# PFC_v1b.net
KiCad netlist of a schematic drawn in EAGLE
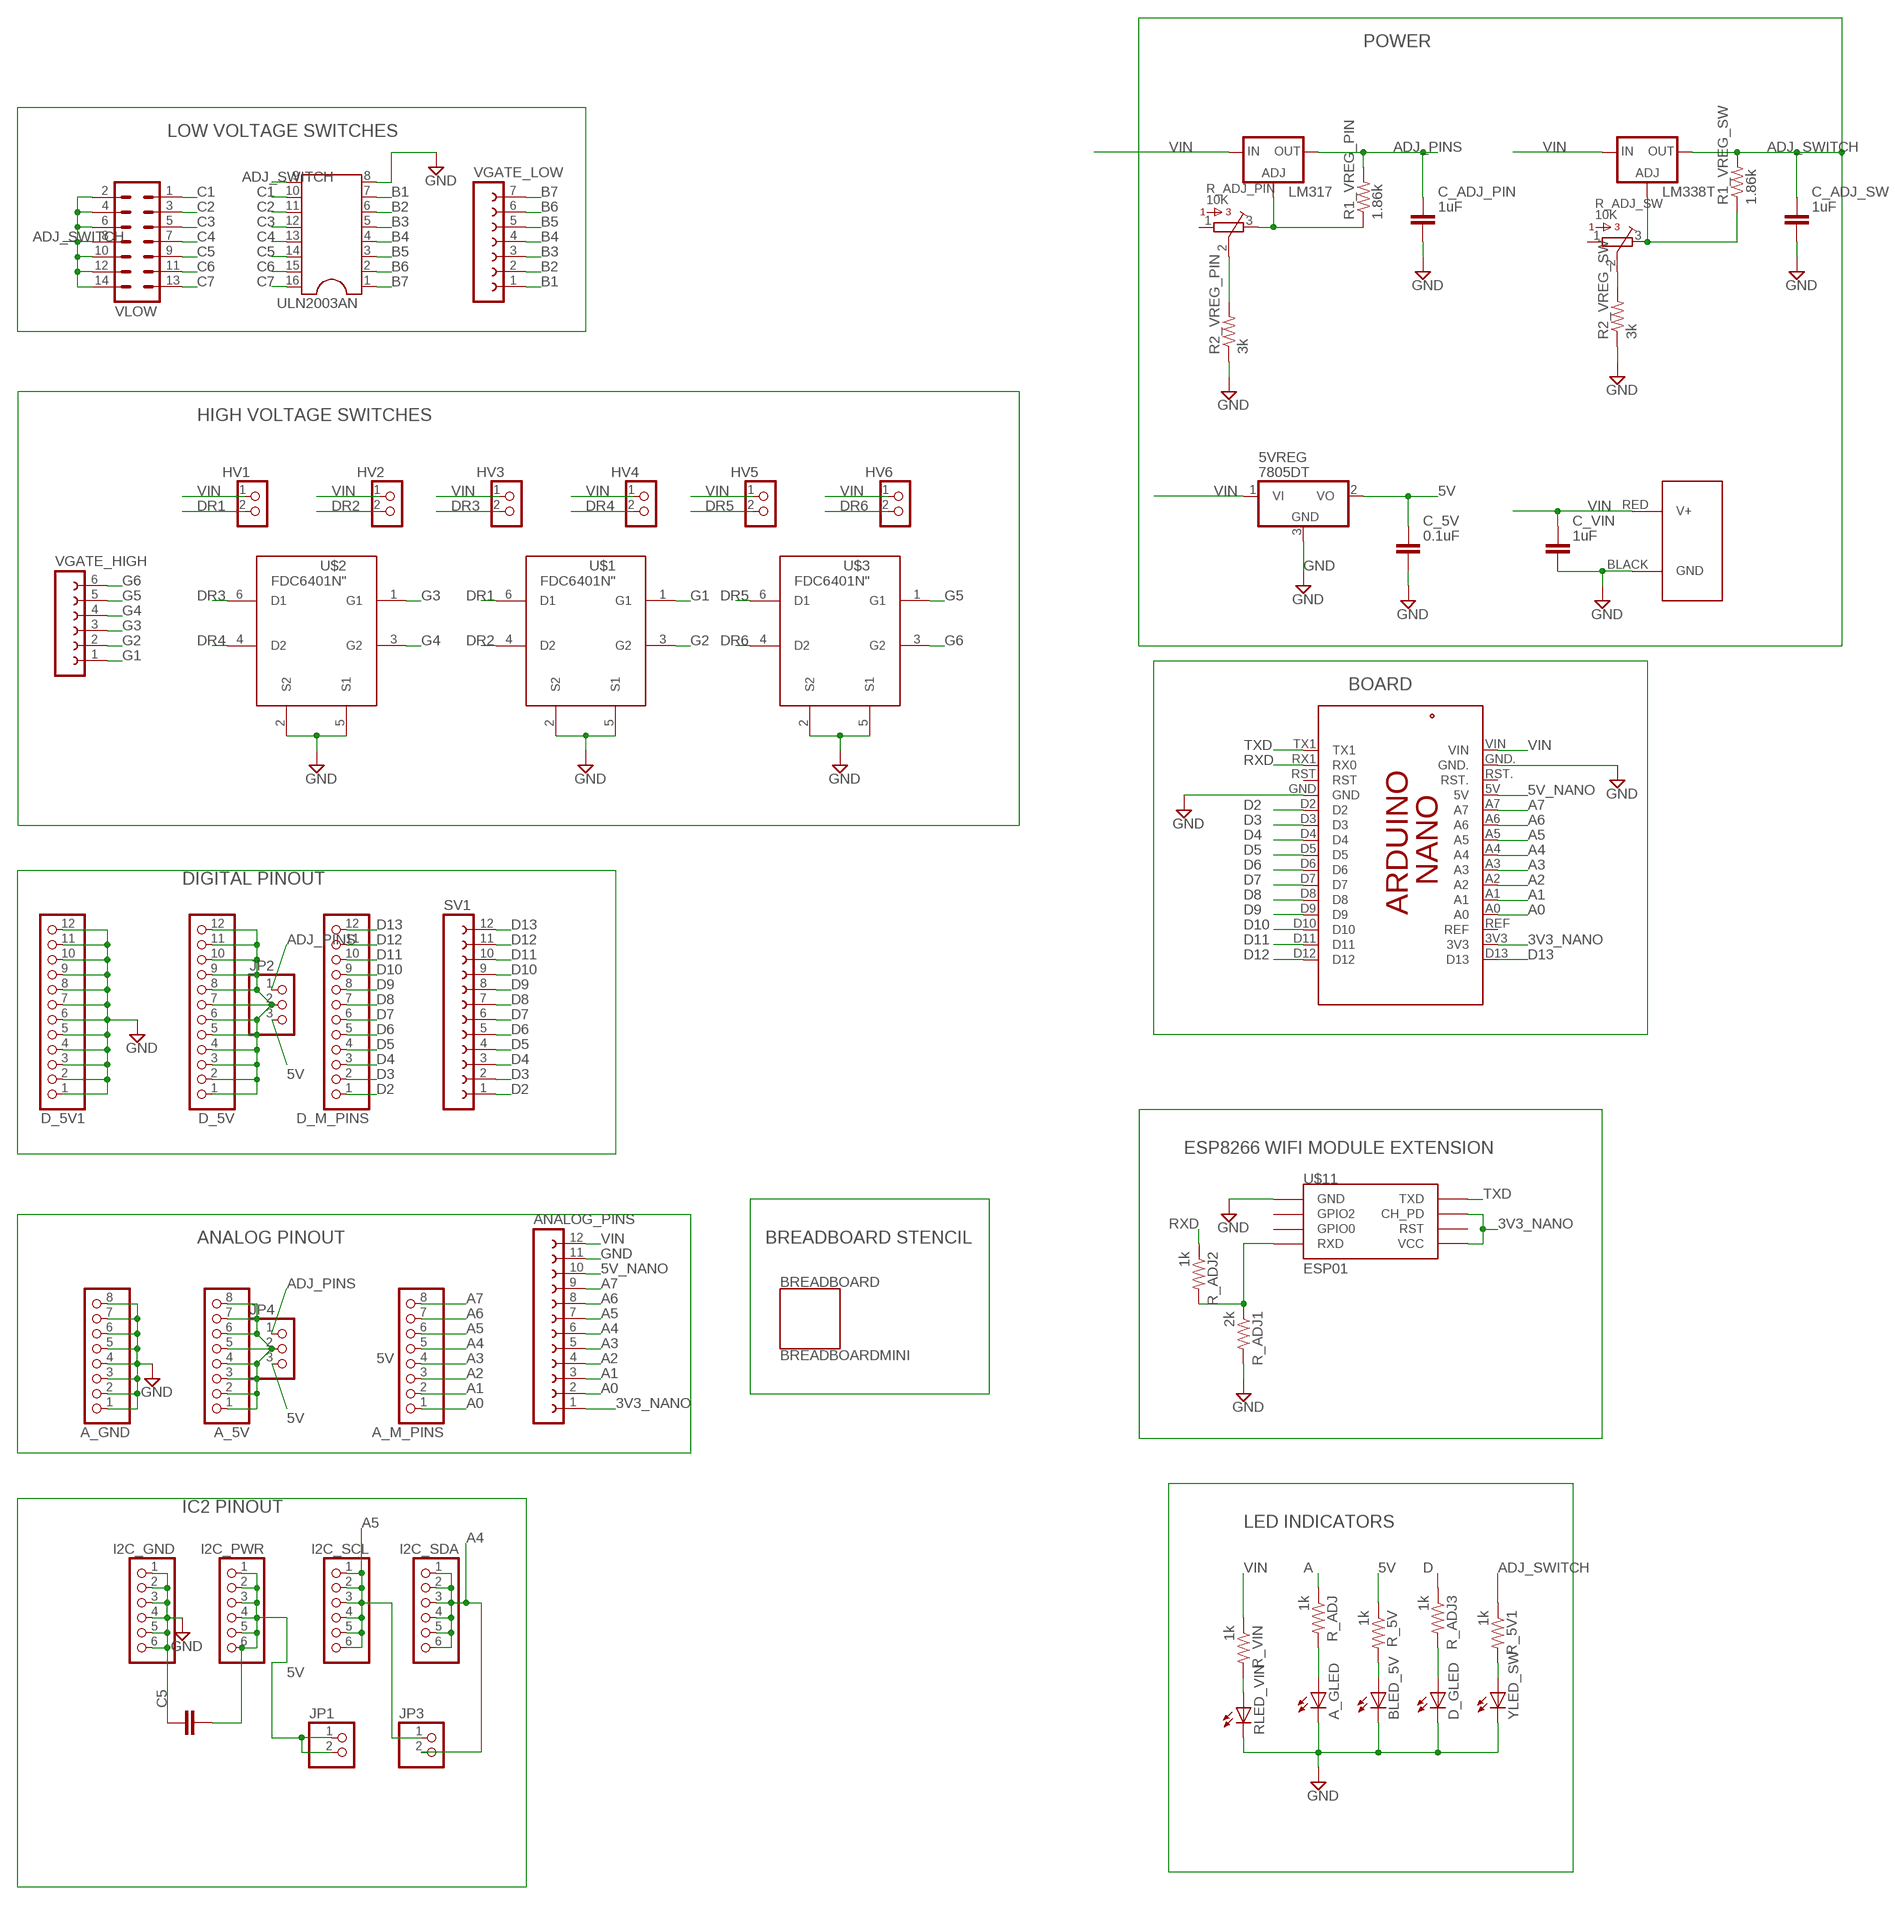
[diagram p0: schematic, sheet 1]

(export (version "E")
  (design (tool "Eeschema 10.0.6"))
  (components
    (comp (ref "5VREG")
      (value "7805DT")
      (footprint "eagle-import:TO252")
      (libsource (lib "eagle-import") (part "78DT05"))
    )
    (comp (ref "ANALOG_PINS")
      (value "FE12-1")
      (footprint "eagle-import:FE12")
      (libsource (lib "eagle-import") (part "FE12-1"))
    )
    (comp (ref "A_5V")
      (value "PINHD-1X8CLEANBIG")
      (footprint "eagle-import:1X08-CLEANBIG")
      (libsource (lib "eagle-import") (part "PINHD-1X8CLEANBIG"))
    )
    (comp (ref "A_GLED")
      (value "LEDCHIP-LED0603")
      (footprint "eagle-import:CHIP-LED0603")
      (libsource (lib "eagle-import") (part "LEDCHIP-LED0603"))
    )
    (comp (ref "A_GND")
      (value "PINHD-1X8CLEANBIG")
      (footprint "eagle-import:1X08-CLEANBIG")
      (libsource (lib "eagle-import") (part "PINHD-1X8CLEANBIG"))
    )
    (comp (ref "A_M_PINS")
      (value "PINHD-1X8CLEANBIG")
      (footprint "eagle-import:1X08-CLEANBIG")
      (libsource (lib "eagle-import") (part "PINHD-1X8CLEANBIG"))
    )
    (comp (ref "BLED_5V")
      (value "LEDCHIP-LED0603")
      (footprint "eagle-import:CHIP-LED0603")
      (libsource (lib "eagle-import") (part "LEDCHIP-LED0603"))
    )
    (comp (ref "BREADBOARD")
      (value "BREADBOARDMINI")
      (footprint "eagle-import:BREADBOARD-MINI")
      (libsource (lib "eagle-import") (part "BREADBOARDMINI"))
    )
    (comp (ref "C5")
      (value "CAPACITOR_NPOL-0603")
      (footprint "eagle-import:C603")
      (libsource (lib "eagle-import") (part "CAPACITOR_NPOL-0603"))
    )
    (comp (ref "C_5V")
      (value "0.1uF")
      (footprint "eagle-import:C603")
      (libsource (lib "eagle-import") (part "CAPACITOR_NPOL-0603"))
    )
    (comp (ref "C_ADJ_PIN")
      (value "1uF")
      (footprint "eagle-import:C603")
      (libsource (lib "eagle-import") (part "CAPACITOR_NPOL-0603"))
    )
    (comp (ref "C_ADJ_SW")
      (value "1uF")
      (footprint "eagle-import:C603")
      (libsource (lib "eagle-import") (part "CAPACITOR_NPOL-0603"))
    )
    (comp (ref "C_VIN")
      (value "1uF")
      (footprint "eagle-import:C603")
      (libsource (lib "eagle-import") (part "CAPACITOR_NPOL-0603"))
    )
    (comp (ref "D_5V")
      (value "PINHD-1X12-CB")
      (footprint "eagle-import:1X12-CB")
      (libsource (lib "eagle-import") (part "PINHD-1X12-CB"))
    )
    (comp (ref "D_5V1")
      (value "PINHD-1X12-CB")
      (footprint "eagle-import:1X12-CB")
      (libsource (lib "eagle-import") (part "PINHD-1X12-CB"))
    )
    (comp (ref "D_GLED")
      (value "LEDCHIP-LED0603")
      (footprint "eagle-import:CHIP-LED0603")
      (libsource (lib "eagle-import") (part "LEDCHIP-LED0603"))
    )
    (comp (ref "D_M_PINS")
      (value "PINHD-1X12-CB")
      (footprint "eagle-import:1X12-CB")
      (libsource (lib "eagle-import") (part "PINHD-1X12-CB"))
    )
    (comp (ref "HV1")
      (value "PINHD-2X1")
      (footprint "eagle-import:2X01")
      (libsource (lib "eagle-import") (part "PINHD-2X1"))
    )
    (comp (ref "HV2")
      (value "PINHD-2X1")
      (footprint "eagle-import:2X01")
      (libsource (lib "eagle-import") (part "PINHD-2X1"))
    )
    (comp (ref "HV3")
      (value "PINHD-2X1")
      (footprint "eagle-import:2X01")
      (libsource (lib "eagle-import") (part "PINHD-2X1"))
    )
    (comp (ref "HV4")
      (value "PINHD-2X1")
      (footprint "eagle-import:2X01")
      (libsource (lib "eagle-import") (part "PINHD-2X1"))
    )
    (comp (ref "HV5")
      (value "PINHD-2X1")
      (footprint "eagle-import:2X01")
      (libsource (lib "eagle-import") (part "PINHD-2X1"))
    )
    (comp (ref "HV6")
      (value "PINHD-2X1")
      (footprint "eagle-import:2X01")
      (libsource (lib "eagle-import") (part "PINHD-2X1"))
    )
    (comp (ref "I2C_GND")
      (value "PINHD-1X6CLEAN")
      (footprint "eagle-import:1X06-CLEAN")
      (libsource (lib "eagle-import") (part "PINHD-1X6CLEAN"))
    )
    (comp (ref "I2C_PWR")
      (value "PINHD-1X6CLEAN")
      (footprint "eagle-import:1X06-CLEAN")
      (libsource (lib "eagle-import") (part "PINHD-1X6CLEAN"))
    )
    (comp (ref "I2C_SCL")
      (value "PINHD-1X6CLEAN")
      (footprint "eagle-import:1X06-CLEAN")
      (libsource (lib "eagle-import") (part "PINHD-1X6CLEAN"))
    )
    (comp (ref "I2C_SDA")
      (value "PINHD-1X6CLEAN")
      (footprint "eagle-import:1X06-CLEAN")
      (libsource (lib "eagle-import") (part "PINHD-1X6CLEAN"))
    )
    (comp (ref "J1")
      (value "POWERPOLE_POWER25A_HORIZONTAL_G2")
      (footprint "eagle-import:POWERPOLE_PAIR_25A_HORIZ_G2")
      (libsource (lib "eagle-import") (part "POWERPOLE_POWER25A_HORIZONTAL_G2"))
    )
    (comp (ref "JP1")
      (value "HEADER-1X2ROUND")
      (footprint "eagle-import:1X02_ROUND")
      (libsource (lib "eagle-import") (part "HEADER-1X2ROUND"))
    )
    (comp (ref "JP2")
      (value "PINHD-1X3CB")
      (footprint "eagle-import:1X03-CLEANBIG")
      (libsource (lib "eagle-import") (part "PINHD-1X3CB"))
    )
    (comp (ref "JP3")
      (value "HEADER-1X2ROUND")
      (footprint "eagle-import:1X02_ROUND")
      (libsource (lib "eagle-import") (part "HEADER-1X2ROUND"))
    )
    (comp (ref "JP4")
      (value "PINHD-1X3CB")
      (footprint "eagle-import:1X03-CLEANBIG")
      (libsource (lib "eagle-import") (part "PINHD-1X3CB"))
    )
    (comp (ref "LM317")
      (value "LM317TL")
      (footprint "eagle-import:317TL")
      (libsource (lib "eagle-import") (part "LM317TL"))
    )
    (comp (ref "LM338T")
      (value "LM138-TL")
      (footprint "eagle-import:TO220L1")
      (libsource (lib "eagle-import") (part "LM138-TL"))
    )
    (comp (ref "PCB1")
      (value "ARDUINO_NANO_SHIELD")
      (footprint "eagle-import:ARDUINO_NANO_SHIELD")
      (libsource (lib "eagle-import") (part "ARDUINO_NANO_SHIELD"))
    )
    (comp (ref "R1_VREG_PIN")
      (value "1.86k")
      (footprint "eagle-import:R0603")
      (libsource (lib "eagle-import") (part "R-US_R0603"))
    )
    (comp (ref "R1_VREG_SW")
      (value "1.86k")
      (footprint "eagle-import:R0603")
      (libsource (lib "eagle-import") (part "R-US_R0603"))
    )
    (comp (ref "R2_VREG_PIN")
      (value "3k")
      (footprint "eagle-import:R0603")
      (libsource (lib "eagle-import") (part "R-US_R0603"))
    )
    (comp (ref "R2_VREG_SW")
      (value "3k")
      (footprint "eagle-import:R0603")
      (libsource (lib "eagle-import") (part "R-US_R0603"))
    )
    (comp (ref "RLED_VIN")
      (value "LEDCHIP-LED0603")
      (footprint "eagle-import:CHIP-LED0603")
      (libsource (lib "eagle-import") (part "LEDCHIP-LED0603"))
    )
    (comp (ref "R_5V")
      (value "1k")
      (footprint "eagle-import:R0603")
      (libsource (lib "eagle-import") (part "R-US_R0603"))
    )
    (comp (ref "R_5V1")
      (value "1k")
      (footprint "eagle-import:R0603")
      (libsource (lib "eagle-import") (part "R-US_R0603"))
    )
    (comp (ref "R_ADJ")
      (value "1k")
      (footprint "eagle-import:R0603")
      (libsource (lib "eagle-import") (part "R-US_R0603"))
    )
    (comp (ref "R_ADJ1")
      (value "2k")
      (footprint "eagle-import:R0603")
      (libsource (lib "eagle-import") (part "R-US_R0603"))
    )
    (comp (ref "R_ADJ2")
      (value "1k")
      (footprint "eagle-import:R0603")
      (libsource (lib "eagle-import") (part "R-US_R0603"))
    )
    (comp (ref "R_ADJ3")
      (value "1k")
      (footprint "eagle-import:R0603")
      (libsource (lib "eagle-import") (part "R-US_R0603"))
    )
    (comp (ref "R_ADJ_PIN")
      (value "10K")
      (footprint "eagle-import:3386P")
      (libsource (lib "eagle-import") (part "3386-P"))
    )
    (comp (ref "R_ADJ_SW")
      (value "10K")
      (footprint "eagle-import:3386P")
      (libsource (lib "eagle-import") (part "3386-P"))
    )
    (comp (ref "R_VIN")
      (value "1k")
      (footprint "eagle-import:R0603")
      (libsource (lib "eagle-import") (part "R-US_R0603"))
    )
    (comp (ref "SV1")
      (value "FE12-1")
      (footprint "eagle-import:FE12")
      (libsource (lib "eagle-import") (part "FE12-1"))
    )
    (comp (ref "U$1")
      (value "FDC6401N\"")
      (footprint "eagle-import:SSOT-6")
      (libsource (lib "eagle-import") (part "FDC6401N{dblquote}"))
    )
    (comp (ref "U$2")
      (value "FDC6401N\"")
      (footprint "eagle-import:SSOT-6")
      (libsource (lib "eagle-import") (part "FDC6401N{dblquote}"))
    )
    (comp (ref "U$3")
      (value "FDC6401N\"")
      (footprint "eagle-import:SSOT-6")
      (libsource (lib "eagle-import") (part "FDC6401N{dblquote}"))
    )
    (comp (ref "U$11")
      (value "ESP01")
      (footprint "eagle-import:ESP01")
      (libsource (lib "eagle-import") (part "ESP01"))
    )
    (comp (ref "ULN2003AN")
      (value "DIL16S")
      (footprint "eagle-import:SOCKET-16")
      (libsource (lib "eagle-import") (part "DIL16S"))
    )
    (comp (ref "VGATE_HIGH")
      (value "FE06-1")
      (footprint "eagle-import:FE06")
      (libsource (lib "eagle-import") (part "FE06-1"))
    )
    (comp (ref "VGATE_LOW")
      (value "FE07-1")
      (footprint "eagle-import:FE07")
      (libsource (lib "eagle-import") (part "FE07-1"))
    )
    (comp (ref "VLOW")
      (value "MA07-2")
      (footprint "eagle-import:MA07-2")
      (libsource (lib "eagle-import") (part "MA07-2"))
    )
    (comp (ref "YLED_SW")
      (value "LEDCHIP-LED0603")
      (footprint "eagle-import:CHIP-LED0603")
      (libsource (lib "eagle-import") (part "LEDCHIP-LED0603"))
    )
  )
  (nets
    (net (code "1") (name "/3V3_NANO") (class "Default")
      (node (ref "ANALOG_PINS") (pin "1") (pinfunction "1_1") (pintype "passive"))
      (node (ref "PCB1") (pin "3V3") (pinfunction "3V3_3V3") (pintype "bidirectional"))
      (node (ref "U$11") (pin "CH_PD") (pinfunction "CH_PD_CH_PD") (pintype "bidirectional"))
      (node (ref "U$11") (pin "VCC") (pinfunction "VCC_VCC") (pintype "bidirectional"))
    )
    (net (code "2") (name "/5V") (class "Default")
      (node (ref "5VREG") (pin "2") (pinfunction "VO_2") (pintype "passive"))
      (node (ref "C5") (pin "2") (pinfunction "2_2") (pintype "passive"))
      (node (ref "C_5V") (pin "1") (pinfunction "1_1") (pintype "passive"))
      (node (ref "I2C_PWR") (pin "1") (pinfunction "1_1") (pintype "passive"))
      (node (ref "I2C_PWR") (pin "2") (pinfunction "2_2") (pintype "passive"))
      (node (ref "I2C_PWR") (pin "3") (pinfunction "3_3") (pintype "passive"))
      (node (ref "I2C_PWR") (pin "4") (pinfunction "4_4") (pintype "passive"))
      (node (ref "I2C_PWR") (pin "5") (pinfunction "5_5") (pintype "passive"))
      (node (ref "I2C_PWR") (pin "6") (pinfunction "6_6") (pintype "passive"))
      (node (ref "JP1") (pin "1") (pinfunction "1_1") (pintype "passive"))
      (node (ref "JP1") (pin "2") (pinfunction "2_2") (pintype "passive"))
      (node (ref "JP2") (pin "3") (pinfunction "3_3") (pintype "passive"))
      (node (ref "JP4") (pin "3") (pinfunction "3_3") (pintype "passive"))
      (node (ref "R_5V") (pin "1") (pinfunction "1_1") (pintype "passive"))
    )
    (net (code "3") (name "/5V_NANO") (class "Default")
      (node (ref "ANALOG_PINS") (pin "10") (pinfunction "10_10") (pintype "passive"))
      (node (ref "PCB1") (pin "5V") (pinfunction "5V_5V") (pintype "bidirectional"))
    )
    (net (code "4") (name "/A") (class "Default")
      (node (ref "A_5V") (pin "1") (pinfunction "1_1") (pintype "passive"))
      (node (ref "A_5V") (pin "2") (pinfunction "2_2") (pintype "passive"))
      (node (ref "A_5V") (pin "3") (pinfunction "3_3") (pintype "passive"))
      (node (ref "A_5V") (pin "4") (pinfunction "4_4") (pintype "passive"))
      (node (ref "A_5V") (pin "5") (pinfunction "5_5") (pintype "passive"))
      (node (ref "A_5V") (pin "6") (pinfunction "6_6") (pintype "passive"))
      (node (ref "A_5V") (pin "7") (pinfunction "7_7") (pintype "passive"))
      (node (ref "A_5V") (pin "8") (pinfunction "8_8") (pintype "passive"))
      (node (ref "JP4") (pin "2") (pinfunction "2_2") (pintype "passive"))
      (node (ref "R_ADJ") (pin "1") (pinfunction "1_1") (pintype "passive"))
    )
    (net (code "5") (name "/A0") (class "Default")
      (node (ref "ANALOG_PINS") (pin "2") (pinfunction "2_2") (pintype "passive"))
      (node (ref "A_M_PINS") (pin "1") (pinfunction "1_1") (pintype "passive"))
      (node (ref "PCB1") (pin "A0") (pinfunction "A0_A0") (pintype "bidirectional"))
    )
    (net (code "6") (name "/A1") (class "Default")
      (node (ref "ANALOG_PINS") (pin "3") (pinfunction "3_3") (pintype "passive"))
      (node (ref "A_M_PINS") (pin "2") (pinfunction "2_2") (pintype "passive"))
      (node (ref "PCB1") (pin "A1") (pinfunction "A1_A1") (pintype "bidirectional"))
    )
    (net (code "7") (name "/A2") (class "Default")
      (node (ref "ANALOG_PINS") (pin "4") (pinfunction "4_4") (pintype "passive"))
      (node (ref "A_M_PINS") (pin "3") (pinfunction "3_3") (pintype "passive"))
      (node (ref "PCB1") (pin "A2") (pinfunction "A2_A2") (pintype "bidirectional"))
    )
    (net (code "8") (name "/A3") (class "Default")
      (node (ref "ANALOG_PINS") (pin "5") (pinfunction "5_5") (pintype "passive"))
      (node (ref "A_M_PINS") (pin "4") (pinfunction "4_4") (pintype "passive"))
      (node (ref "PCB1") (pin "A3") (pinfunction "A3_A3") (pintype "bidirectional"))
    )
    (net (code "9") (name "/A4") (class "Default")
      (node (ref "ANALOG_PINS") (pin "6") (pinfunction "6_6") (pintype "passive"))
      (node (ref "A_M_PINS") (pin "5") (pinfunction "5_5") (pintype "passive"))
      (node (ref "I2C_SDA") (pin "1") (pinfunction "1_1") (pintype "passive"))
      (node (ref "I2C_SDA") (pin "2") (pinfunction "2_2") (pintype "passive"))
      (node (ref "I2C_SDA") (pin "3") (pinfunction "3_3") (pintype "passive"))
      (node (ref "I2C_SDA") (pin "4") (pinfunction "4_4") (pintype "passive"))
      (node (ref "I2C_SDA") (pin "5") (pinfunction "5_5") (pintype "passive"))
      (node (ref "I2C_SDA") (pin "6") (pinfunction "6_6") (pintype "passive"))
      (node (ref "JP3") (pin "2") (pinfunction "2_2") (pintype "passive"))
      (node (ref "PCB1") (pin "A4") (pinfunction "A4_A4") (pintype "bidirectional"))
    )
    (net (code "10") (name "/A5") (class "Default")
      (node (ref "ANALOG_PINS") (pin "7") (pinfunction "7_7") (pintype "passive"))
      (node (ref "A_M_PINS") (pin "6") (pinfunction "6_6") (pintype "passive"))
      (node (ref "I2C_SCL") (pin "1") (pinfunction "1_1") (pintype "passive"))
      (node (ref "I2C_SCL") (pin "2") (pinfunction "2_2") (pintype "passive"))
      (node (ref "I2C_SCL") (pin "3") (pinfunction "3_3") (pintype "passive"))
      (node (ref "I2C_SCL") (pin "4") (pinfunction "4_4") (pintype "passive"))
      (node (ref "I2C_SCL") (pin "5") (pinfunction "5_5") (pintype "passive"))
      (node (ref "I2C_SCL") (pin "6") (pinfunction "6_6") (pintype "passive"))
      (node (ref "JP3") (pin "1") (pinfunction "1_1") (pintype "passive"))
      (node (ref "PCB1") (pin "A5") (pinfunction "A5_A5") (pintype "bidirectional"))
    )
    (net (code "11") (name "/A6") (class "Default")
      (node (ref "ANALOG_PINS") (pin "8") (pinfunction "8_8") (pintype "passive"))
      (node (ref "A_M_PINS") (pin "7") (pinfunction "7_7") (pintype "passive"))
      (node (ref "PCB1") (pin "A6") (pinfunction "A6_A6") (pintype "bidirectional"))
    )
    (net (code "12") (name "/A7") (class "Default")
      (node (ref "ANALOG_PINS") (pin "9") (pinfunction "9_9") (pintype "passive"))
      (node (ref "A_M_PINS") (pin "8") (pinfunction "8_8") (pintype "passive"))
      (node (ref "PCB1") (pin "A7") (pinfunction "A7_A7") (pintype "bidirectional"))
    )
    (net (code "13") (name "/ADJ_PINS") (class "Default")
      (node (ref "C_ADJ_PIN") (pin "1") (pinfunction "1_1") (pintype "passive"))
      (node (ref "JP2") (pin "1") (pinfunction "1_1") (pintype "passive"))
      (node (ref "JP4") (pin "1") (pinfunction "1_1") (pintype "passive"))
      (node (ref "LM317") (pin "2") (pinfunction "OUT_2") (pintype "passive"))
      (node (ref "R1_VREG_PIN") (pin "2") (pinfunction "2_2") (pintype "passive"))
    )
    (net (code "14") (name "/ADJ_SWITCH") (class "Default")
      (node (ref "C_ADJ_SW") (pin "1") (pinfunction "1_1") (pintype "passive"))
      (node (ref "LM338T") (pin "2") (pinfunction "OUT_2") (pintype "passive"))
      (node (ref "R1_VREG_SW") (pin "2") (pinfunction "2_2") (pintype "passive"))
      (node (ref "R_5V1") (pin "1") (pinfunction "1_1") (pintype "passive"))
      (node (ref "ULN2003AN") (pin "9") (pinfunction "9_9") (pintype "passive"))
      (node (ref "VLOW") (pin "10") (pinfunction "10_10") (pintype "passive"))
      (node (ref "VLOW") (pin "12") (pinfunction "12_12") (pintype "passive"))
      (node (ref "VLOW") (pin "14") (pinfunction "14_14") (pintype "passive"))
      (node (ref "VLOW") (pin "2") (pinfunction "2_2") (pintype "passive"))
      (node (ref "VLOW") (pin "4") (pinfunction "4_4") (pintype "passive"))
      (node (ref "VLOW") (pin "6") (pinfunction "6_6") (pintype "passive"))
      (node (ref "VLOW") (pin "8") (pinfunction "8_8") (pintype "passive"))
    )
    (net (code "15") (name "/B1") (class "Default")
      (node (ref "ULN2003AN") (pin "7") (pinfunction "7_7") (pintype "passive"))
      (node (ref "VGATE_LOW") (pin "1") (pinfunction "1_1") (pintype "passive"))
    )
    (net (code "16") (name "/B2") (class "Default")
      (node (ref "ULN2003AN") (pin "6") (pinfunction "6_6") (pintype "passive"))
      (node (ref "VGATE_LOW") (pin "2") (pinfunction "2_2") (pintype "passive"))
    )
    (net (code "17") (name "/B3") (class "Default")
      (node (ref "ULN2003AN") (pin "5") (pinfunction "5_5") (pintype "passive"))
      (node (ref "VGATE_LOW") (pin "3") (pinfunction "3_3") (pintype "passive"))
    )
    (net (code "18") (name "/B4") (class "Default")
      (node (ref "ULN2003AN") (pin "4") (pinfunction "4_4") (pintype "passive"))
      (node (ref "VGATE_LOW") (pin "4") (pinfunction "4_4") (pintype "passive"))
    )
    (net (code "19") (name "/B5") (class "Default")
      (node (ref "ULN2003AN") (pin "3") (pinfunction "3_3") (pintype "passive"))
      (node (ref "VGATE_LOW") (pin "5") (pinfunction "5_5") (pintype "passive"))
    )
    (net (code "20") (name "/B6") (class "Default")
      (node (ref "ULN2003AN") (pin "2") (pinfunction "2_2") (pintype "passive"))
      (node (ref "VGATE_LOW") (pin "6") (pinfunction "6_6") (pintype "passive"))
    )
    (net (code "21") (name "/B7") (class "Default")
      (node (ref "ULN2003AN") (pin "1") (pinfunction "1_1") (pintype "passive"))
      (node (ref "VGATE_LOW") (pin "7") (pinfunction "7_7") (pintype "passive"))
    )
    (net (code "22") (name "/C1") (class "Default")
      (node (ref "ULN2003AN") (pin "10") (pinfunction "10_10") (pintype "passive"))
      (node (ref "VLOW") (pin "1") (pinfunction "1_1") (pintype "passive"))
    )
    (net (code "23") (name "/C2") (class "Default")
      (node (ref "ULN2003AN") (pin "11") (pinfunction "11_11") (pintype "passive"))
      (node (ref "VLOW") (pin "3") (pinfunction "3_3") (pintype "passive"))
    )
    (net (code "24") (name "/C3") (class "Default")
      (node (ref "ULN2003AN") (pin "12") (pinfunction "12_12") (pintype "passive"))
      (node (ref "VLOW") (pin "5") (pinfunction "5_5") (pintype "passive"))
    )
    (net (code "25") (name "/C4") (class "Default")
      (node (ref "ULN2003AN") (pin "13") (pinfunction "13_13") (pintype "passive"))
      (node (ref "VLOW") (pin "7") (pinfunction "7_7") (pintype "passive"))
    )
    (net (code "26") (name "/C5") (class "Default")
      (node (ref "ULN2003AN") (pin "14") (pinfunction "14_14") (pintype "passive"))
      (node (ref "VLOW") (pin "9") (pinfunction "9_9") (pintype "passive"))
    )
    (net (code "27") (name "/C6") (class "Default")
      (node (ref "ULN2003AN") (pin "15") (pinfunction "15_15") (pintype "passive"))
      (node (ref "VLOW") (pin "11") (pinfunction "11_11") (pintype "passive"))
    )
    (net (code "28") (name "/C7") (class "Default")
      (node (ref "ULN2003AN") (pin "16") (pinfunction "16_16") (pintype "passive"))
      (node (ref "VLOW") (pin "13") (pinfunction "13_13") (pintype "passive"))
    )
    (net (code "29") (name "/D") (class "Default")
      (node (ref "D_5V") (pin "1") (pinfunction "1_1") (pintype "passive"))
      (node (ref "D_5V") (pin "10") (pinfunction "10_10") (pintype "passive"))
      (node (ref "D_5V") (pin "11") (pinfunction "11_11") (pintype "passive"))
      (node (ref "D_5V") (pin "12") (pinfunction "12_12") (pintype "passive"))
      (node (ref "D_5V") (pin "2") (pinfunction "2_2") (pintype "passive"))
      (node (ref "D_5V") (pin "3") (pinfunction "3_3") (pintype "passive"))
      (node (ref "D_5V") (pin "4") (pinfunction "4_4") (pintype "passive"))
      (node (ref "D_5V") (pin "5") (pinfunction "5_5") (pintype "passive"))
      (node (ref "D_5V") (pin "6") (pinfunction "6_6") (pintype "passive"))
      (node (ref "D_5V") (pin "7") (pinfunction "7_7") (pintype "passive"))
      (node (ref "D_5V") (pin "8") (pinfunction "8_8") (pintype "passive"))
      (node (ref "D_5V") (pin "9") (pinfunction "9_9") (pintype "passive"))
      (node (ref "JP2") (pin "2") (pinfunction "2_2") (pintype "passive"))
      (node (ref "R_ADJ3") (pin "1") (pinfunction "1_1") (pintype "passive"))
    )
    (net (code "30") (name "/D2") (class "Default")
      (node (ref "D_M_PINS") (pin "1") (pinfunction "1_1") (pintype "passive"))
      (node (ref "PCB1") (pin "D2") (pinfunction "D2_D2") (pintype "bidirectional"))
      (node (ref "SV1") (pin "1") (pinfunction "1_1") (pintype "passive"))
    )
    (net (code "31") (name "/D3") (class "Default")
      (node (ref "D_M_PINS") (pin "2") (pinfunction "2_2") (pintype "passive"))
      (node (ref "PCB1") (pin "D3") (pinfunction "D3_D3") (pintype "bidirectional"))
      (node (ref "SV1") (pin "2") (pinfunction "2_2") (pintype "passive"))
    )
    (net (code "32") (name "/D4") (class "Default")
      (node (ref "D_M_PINS") (pin "3") (pinfunction "3_3") (pintype "passive"))
      (node (ref "PCB1") (pin "D4") (pinfunction "D4_D4") (pintype "bidirectional"))
      (node (ref "SV1") (pin "3") (pinfunction "3_3") (pintype "passive"))
    )
    (net (code "33") (name "/D5") (class "Default")
      (node (ref "D_M_PINS") (pin "4") (pinfunction "4_4") (pintype "passive"))
      (node (ref "PCB1") (pin "D5") (pinfunction "D5_D5") (pintype "bidirectional"))
      (node (ref "SV1") (pin "4") (pinfunction "4_4") (pintype "passive"))
    )
    (net (code "34") (name "/D6") (class "Default")
      (node (ref "D_M_PINS") (pin "5") (pinfunction "5_5") (pintype "passive"))
      (node (ref "PCB1") (pin "D6") (pinfunction "D6_D6") (pintype "bidirectional"))
      (node (ref "SV1") (pin "5") (pinfunction "5_5") (pintype "passive"))
    )
    (net (code "35") (name "/D7") (class "Default")
      (node (ref "D_M_PINS") (pin "6") (pinfunction "6_6") (pintype "passive"))
      (node (ref "PCB1") (pin "D7") (pinfunction "D7_D7") (pintype "bidirectional"))
      (node (ref "SV1") (pin "6") (pinfunction "6_6") (pintype "passive"))
    )
    (net (code "36") (name "/D8") (class "Default")
      (node (ref "D_M_PINS") (pin "7") (pinfunction "7_7") (pintype "passive"))
      (node (ref "PCB1") (pin "D8") (pinfunction "D8_D8") (pintype "bidirectional"))
      (node (ref "SV1") (pin "7") (pinfunction "7_7") (pintype "passive"))
    )
    (net (code "37") (name "/D9") (class "Default")
      (node (ref "D_M_PINS") (pin "8") (pinfunction "8_8") (pintype "passive"))
      (node (ref "PCB1") (pin "D9") (pinfunction "D9_D9") (pintype "bidirectional"))
      (node (ref "SV1") (pin "8") (pinfunction "8_8") (pintype "passive"))
    )
    (net (code "38") (name "/D10") (class "Default")
      (node (ref "D_M_PINS") (pin "9") (pinfunction "9_9") (pintype "passive"))
      (node (ref "PCB1") (pin "D10") (pinfunction "D10_D10") (pintype "bidirectional"))
      (node (ref "SV1") (pin "9") (pinfunction "9_9") (pintype "passive"))
    )
    (net (code "39") (name "/D11") (class "Default")
      (node (ref "D_M_PINS") (pin "10") (pinfunction "10_10") (pintype "passive"))
      (node (ref "PCB1") (pin "D11") (pinfunction "D11_D11") (pintype "bidirectional"))
      (node (ref "SV1") (pin "10") (pinfunction "10_10") (pintype "passive"))
    )
    (net (code "40") (name "/D12") (class "Default")
      (node (ref "D_M_PINS") (pin "11") (pinfunction "11_11") (pintype "passive"))
      (node (ref "PCB1") (pin "D12") (pinfunction "D12_D12") (pintype "bidirectional"))
      (node (ref "SV1") (pin "11") (pinfunction "11_11") (pintype "passive"))
    )
    (net (code "41") (name "/D13") (class "Default")
      (node (ref "D_M_PINS") (pin "12") (pinfunction "12_12") (pintype "passive"))
      (node (ref "PCB1") (pin "D13") (pinfunction "D13_D13") (pintype "bidirectional"))
      (node (ref "SV1") (pin "12") (pinfunction "12_12") (pintype "passive"))
    )
    (net (code "42") (name "/DR1") (class "Default")
      (node (ref "HV1") (pin "2") (pinfunction "3_2") (pintype "passive"))
      (node (ref "U$1") (pin "6") (pinfunction "D1_6") (pintype "bidirectional"))
    )
    (net (code "43") (name "/DR2") (class "Default")
      (node (ref "HV2") (pin "2") (pinfunction "3_2") (pintype "passive"))
      (node (ref "U$1") (pin "4") (pinfunction "D2_4") (pintype "bidirectional"))
    )
    (net (code "44") (name "/DR3") (class "Default")
      (node (ref "HV3") (pin "2") (pinfunction "3_2") (pintype "passive"))
      (node (ref "U$2") (pin "6") (pinfunction "D1_6") (pintype "bidirectional"))
    )
    (net (code "45") (name "/DR4") (class "Default")
      (node (ref "HV4") (pin "2") (pinfunction "3_2") (pintype "passive"))
      (node (ref "U$2") (pin "4") (pinfunction "D2_4") (pintype "bidirectional"))
    )
    (net (code "46") (name "/DR5") (class "Default")
      (node (ref "HV5") (pin "2") (pinfunction "3_2") (pintype "passive"))
      (node (ref "U$3") (pin "6") (pinfunction "D1_6") (pintype "bidirectional"))
    )
    (net (code "47") (name "/DR6") (class "Default")
      (node (ref "HV6") (pin "2") (pinfunction "3_2") (pintype "passive"))
      (node (ref "U$3") (pin "4") (pinfunction "D2_4") (pintype "bidirectional"))
    )
    (net (code "48") (name "/G1") (class "Default")
      (node (ref "U$1") (pin "1") (pinfunction "G1_1") (pintype "bidirectional"))
      (node (ref "VGATE_HIGH") (pin "1") (pinfunction "1_1") (pintype "passive"))
    )
    (net (code "49") (name "/G2") (class "Default")
      (node (ref "U$1") (pin "3") (pinfunction "G2_3") (pintype "bidirectional"))
      (node (ref "VGATE_HIGH") (pin "2") (pinfunction "2_2") (pintype "passive"))
    )
    (net (code "50") (name "/G3") (class "Default")
      (node (ref "U$2") (pin "1") (pinfunction "G1_1") (pintype "bidirectional"))
      (node (ref "VGATE_HIGH") (pin "3") (pinfunction "3_3") (pintype "passive"))
    )
    (net (code "51") (name "/G4") (class "Default")
      (node (ref "U$2") (pin "3") (pinfunction "G2_3") (pintype "bidirectional"))
      (node (ref "VGATE_HIGH") (pin "4") (pinfunction "4_4") (pintype "passive"))
    )
    (net (code "52") (name "/G5") (class "Default")
      (node (ref "U$3") (pin "1") (pinfunction "G1_1") (pintype "bidirectional"))
      (node (ref "VGATE_HIGH") (pin "5") (pinfunction "5_5") (pintype "passive"))
    )
    (net (code "53") (name "/G6") (class "Default")
      (node (ref "U$3") (pin "3") (pinfunction "G2_3") (pintype "bidirectional"))
      (node (ref "VGATE_HIGH") (pin "6") (pinfunction "6_6") (pintype "passive"))
    )
    (net (code "54") (name "/RXD") (class "Default")
      (node (ref "PCB1") (pin "RX1") (pinfunction "RX0_RX1") (pintype "bidirectional"))
      (node (ref "R_ADJ2") (pin "1") (pinfunction "1_1") (pintype "passive"))
    )
    (net (code "55") (name "/TXD") (class "Default")
      (node (ref "PCB1") (pin "TX1") (pinfunction "TX1_TX1") (pintype "bidirectional"))
      (node (ref "U$11") (pin "TX") (pinfunction "TXD_TX") (pintype "bidirectional"))
    )
    (net (code "56") (name "/VIN") (class "Default")
      (node (ref "5VREG") (pin "1") (pinfunction "VI_1") (pintype "input"))
      (node (ref "ANALOG_PINS") (pin "12") (pinfunction "12_12") (pintype "passive"))
      (node (ref "C_VIN") (pin "1") (pinfunction "1_1") (pintype "passive"))
      (node (ref "HV1") (pin "1") (pinfunction "1_1") (pintype "passive"))
      (node (ref "HV2") (pin "1") (pinfunction "1_1") (pintype "passive"))
      (node (ref "HV3") (pin "1") (pinfunction "1_1") (pintype "passive"))
      (node (ref "HV4") (pin "1") (pinfunction "1_1") (pintype "passive"))
      (node (ref "HV5") (pin "1") (pinfunction "1_1") (pintype "passive"))
      (node (ref "HV6") (pin "1") (pinfunction "1_1") (pintype "passive"))
      (node (ref "J1") (pin "RED") (pinfunction "V+_RED") (pintype "power_in"))
      (node (ref "LM317") (pin "3") (pinfunction "IN_3") (pintype "input"))
      (node (ref "LM338T") (pin "3") (pinfunction "IN_3") (pintype "input"))
      (node (ref "PCB1") (pin "VIN") (pinfunction "VIN_VIN") (pintype "bidirectional"))
      (node (ref "R_VIN") (pin "1") (pinfunction "1_1") (pintype "passive"))
    )
    (net (code "57") (name "GND") (class "Default")
      (node (ref "5VREG") (pin "3") (pinfunction "GND_3") (pintype "passive"))
      (node (ref "ANALOG_PINS") (pin "11") (pinfunction "11_11") (pintype "passive"))
      (node (ref "A_GLED") (pin "C") (pinfunction "C_C") (pintype "passive"))
      (node (ref "A_GND") (pin "1") (pinfunction "1_1") (pintype "passive"))
      (node (ref "A_GND") (pin "2") (pinfunction "2_2") (pintype "passive"))
      (node (ref "A_GND") (pin "3") (pinfunction "3_3") (pintype "passive"))
      (node (ref "A_GND") (pin "4") (pinfunction "4_4") (pintype "passive"))
      (node (ref "A_GND") (pin "5") (pinfunction "5_5") (pintype "passive"))
      (node (ref "A_GND") (pin "6") (pinfunction "6_6") (pintype "passive"))
      (node (ref "A_GND") (pin "7") (pinfunction "7_7") (pintype "passive"))
      (node (ref "A_GND") (pin "8") (pinfunction "8_8") (pintype "passive"))
      (node (ref "BLED_5V") (pin "C") (pinfunction "C_C") (pintype "passive"))
      (node (ref "C5") (pin "1") (pinfunction "1_1") (pintype "passive"))
      (node (ref "C_5V") (pin "2") (pinfunction "2_2") (pintype "passive"))
      (node (ref "C_ADJ_PIN") (pin "2") (pinfunction "2_2") (pintype "passive"))
      (node (ref "C_ADJ_SW") (pin "2") (pinfunction "2_2") (pintype "passive"))
      (node (ref "C_VIN") (pin "2") (pinfunction "2_2") (pintype "passive"))
      (node (ref "D_5V1") (pin "1") (pinfunction "1_1") (pintype "passive"))
      (node (ref "D_5V1") (pin "10") (pinfunction "10_10") (pintype "passive"))
      (node (ref "D_5V1") (pin "11") (pinfunction "11_11") (pintype "passive"))
      (node (ref "D_5V1") (pin "12") (pinfunction "12_12") (pintype "passive"))
      (node (ref "D_5V1") (pin "2") (pinfunction "2_2") (pintype "passive"))
      (node (ref "D_5V1") (pin "3") (pinfunction "3_3") (pintype "passive"))
      (node (ref "D_5V1") (pin "4") (pinfunction "4_4") (pintype "passive"))
      (node (ref "D_5V1") (pin "5") (pinfunction "5_5") (pintype "passive"))
      (node (ref "D_5V1") (pin "6") (pinfunction "6_6") (pintype "passive"))
      (node (ref "D_5V1") (pin "7") (pinfunction "7_7") (pintype "passive"))
      (node (ref "D_5V1") (pin "8") (pinfunction "8_8") (pintype "passive"))
      (node (ref "D_5V1") (pin "9") (pinfunction "9_9") (pintype "passive"))
      (node (ref "D_GLED") (pin "C") (pinfunction "C_C") (pintype "passive"))
      (node (ref "I2C_GND") (pin "1") (pinfunction "1_1") (pintype "passive"))
      (node (ref "I2C_GND") (pin "2") (pinfunction "2_2") (pintype "passive"))
      (node (ref "I2C_GND") (pin "3") (pinfunction "3_3") (pintype "passive"))
      (node (ref "I2C_GND") (pin "4") (pinfunction "4_4") (pintype "passive"))
      (node (ref "I2C_GND") (pin "5") (pinfunction "5_5") (pintype "passive"))
      (node (ref "I2C_GND") (pin "6") (pinfunction "6_6") (pintype "passive"))
      (node (ref "J1") (pin "BLACK") (pinfunction "GND_BLACK") (pintype "power_in"))
      (node (ref "PCB1") (pin "GND") (pinfunction "GND_GND") (pintype "bidirectional"))
      (node (ref "PCB1") (pin "GND.") (pinfunction "GND._GND.") (pintype "bidirectional"))
      (node (ref "R2_VREG_PIN") (pin "1") (pinfunction "1_1") (pintype "passive"))
      (node (ref "R2_VREG_SW") (pin "1") (pinfunction "1_1") (pintype "passive"))
      (node (ref "RLED_VIN") (pin "C") (pinfunction "C_C") (pintype "passive"))
      (node (ref "R_ADJ1") (pin "2") (pinfunction "2_2") (pintype "passive"))
      (node (ref "U$1") (pin "2") (pinfunction "S2_2") (pintype "bidirectional"))
      (node (ref "U$1") (pin "5") (pinfunction "S1_5") (pintype "bidirectional"))
      (node (ref "U$11") (pin "GND") (pinfunction "GND_GND") (pintype "bidirectional"))
      (node (ref "U$2") (pin "2") (pinfunction "S2_2") (pintype "bidirectional"))
      (node (ref "U$2") (pin "5") (pinfunction "S1_5") (pintype "bidirectional"))
      (node (ref "U$3") (pin "2") (pinfunction "S2_2") (pintype "bidirectional"))
      (node (ref "U$3") (pin "5") (pinfunction "S1_5") (pintype "bidirectional"))
      (node (ref "ULN2003AN") (pin "8") (pinfunction "8_8") (pintype "passive"))
      (node (ref "YLED_SW") (pin "C") (pinfunction "C_C") (pintype "passive"))
    )
    (net (code "58") (name "Net-(A_GLED-PadA)") (class "Default")
      (node (ref "A_GLED") (pin "A") (pinfunction "A_A") (pintype "passive"))
      (node (ref "R_ADJ") (pin "2") (pinfunction "2_2") (pintype "passive"))
    )
    (net (code "59") (name "Net-(BLED_5V-PadA)") (class "Default")
      (node (ref "BLED_5V") (pin "A") (pinfunction "A_A") (pintype "passive"))
      (node (ref "R_5V") (pin "2") (pinfunction "2_2") (pintype "passive"))
    )
    (net (code "60") (name "Net-(D_GLED-PadA)") (class "Default")
      (node (ref "D_GLED") (pin "A") (pinfunction "A_A") (pintype "passive"))
      (node (ref "R_ADJ3") (pin "2") (pinfunction "2_2") (pintype "passive"))
    )
    (net (code "61") (name "Net-(LM317-ADJ)") (class "Default")
      (node (ref "LM317") (pin "1") (pinfunction "ADJ_1") (pintype "input"))
      (node (ref "R1_VREG_PIN") (pin "1") (pinfunction "1_1") (pintype "passive"))
      (node (ref "R_ADJ_PIN") (pin "3") (pinfunction "3_3") (pintype "passive"))
    )
    (net (code "62") (name "Net-(LM338T-ADJ)") (class "Default")
      (node (ref "LM338T") (pin "1") (pinfunction "ADJ_1") (pintype "input"))
      (node (ref "R1_VREG_SW") (pin "1") (pinfunction "1_1") (pintype "passive"))
      (node (ref "R_ADJ_SW") (pin "3") (pinfunction "3_3") (pintype "passive"))
    )
    (net (code "63") (name "Net-(R2_VREG_PIN-Pad2)") (class "Default")
      (node (ref "R2_VREG_PIN") (pin "2") (pinfunction "2_2") (pintype "passive"))
      (node (ref "R_ADJ_PIN") (pin "2") (pinfunction "2_2") (pintype "passive"))
    )
    (net (code "64") (name "Net-(R2_VREG_SW-Pad2)") (class "Default")
      (node (ref "R2_VREG_SW") (pin "2") (pinfunction "2_2") (pintype "passive"))
      (node (ref "R_ADJ_SW") (pin "2") (pinfunction "2_2") (pintype "passive"))
    )
    (net (code "65") (name "Net-(RLED_VIN-PadA)") (class "Default")
      (node (ref "RLED_VIN") (pin "A") (pinfunction "A_A") (pintype "passive"))
      (node (ref "R_VIN") (pin "2") (pinfunction "2_2") (pintype "passive"))
    )
    (net (code "66") (name "Net-(R_5V1-Pad2)") (class "Default")
      (node (ref "R_5V1") (pin "2") (pinfunction "2_2") (pintype "passive"))
      (node (ref "YLED_SW") (pin "A") (pinfunction "A_A") (pintype "passive"))
    )
    (net (code "67") (name "Net-(U$11-RXD)") (class "Default")
      (node (ref "R_ADJ1") (pin "1") (pinfunction "1_1") (pintype "passive"))
      (node (ref "R_ADJ2") (pin "2") (pinfunction "2_2") (pintype "passive"))
      (node (ref "U$11") (pin "RX") (pinfunction "RXD_RX") (pintype "bidirectional"))
    )
    (net (code "68") (name "unconnected-(PCB1-PadREF)") (class "Default")
      (node (ref "PCB1") (pin "REF") (pinfunction "REF_REF") (pintype "bidirectional"))
    )
    (net (code "69") (name "unconnected-(PCB1-PadRST)") (class "Default")
      (node (ref "PCB1") (pin "RST") (pinfunction "RST_RST") (pintype "bidirectional"))
    )
    (net (code "70") (name "unconnected-(PCB1-PadRST.)") (class "Default")
      (node (ref "PCB1") (pin "RST.") (pinfunction "RST._RST.") (pintype "bidirectional"))
    )
    (net (code "71") (name "unconnected-(R_ADJ_PIN-Pad1)") (class "Default")
      (node (ref "R_ADJ_PIN") (pin "1") (pinfunction "1_1") (pintype "passive"))
    )
    (net (code "72") (name "unconnected-(R_ADJ_SW-Pad1)") (class "Default")
      (node (ref "R_ADJ_SW") (pin "1") (pinfunction "1_1") (pintype "passive"))
    )
    (net (code "73") (name "unconnected-(U$11-PadGPIO0)") (class "Default")
      (node (ref "U$11") (pin "GPIO0") (pinfunction "GPIO0_GPIO0") (pintype "bidirectional"))
    )
    (net (code "74") (name "unconnected-(U$11-PadGPIO2)") (class "Default")
      (node (ref "U$11") (pin "GPIO2") (pinfunction "GPIO2_GPIO2") (pintype "bidirectional"))
    )
    (net (code "75") (name "unconnected-(U$11-PadRST)") (class "Default")
      (node (ref "U$11") (pin "RST") (pinfunction "RST_RST") (pintype "bidirectional"))
    )
  )
)
